# DM1097_Power_Supply.net
KiCad netlist of a schematic drawn in Altium Designer
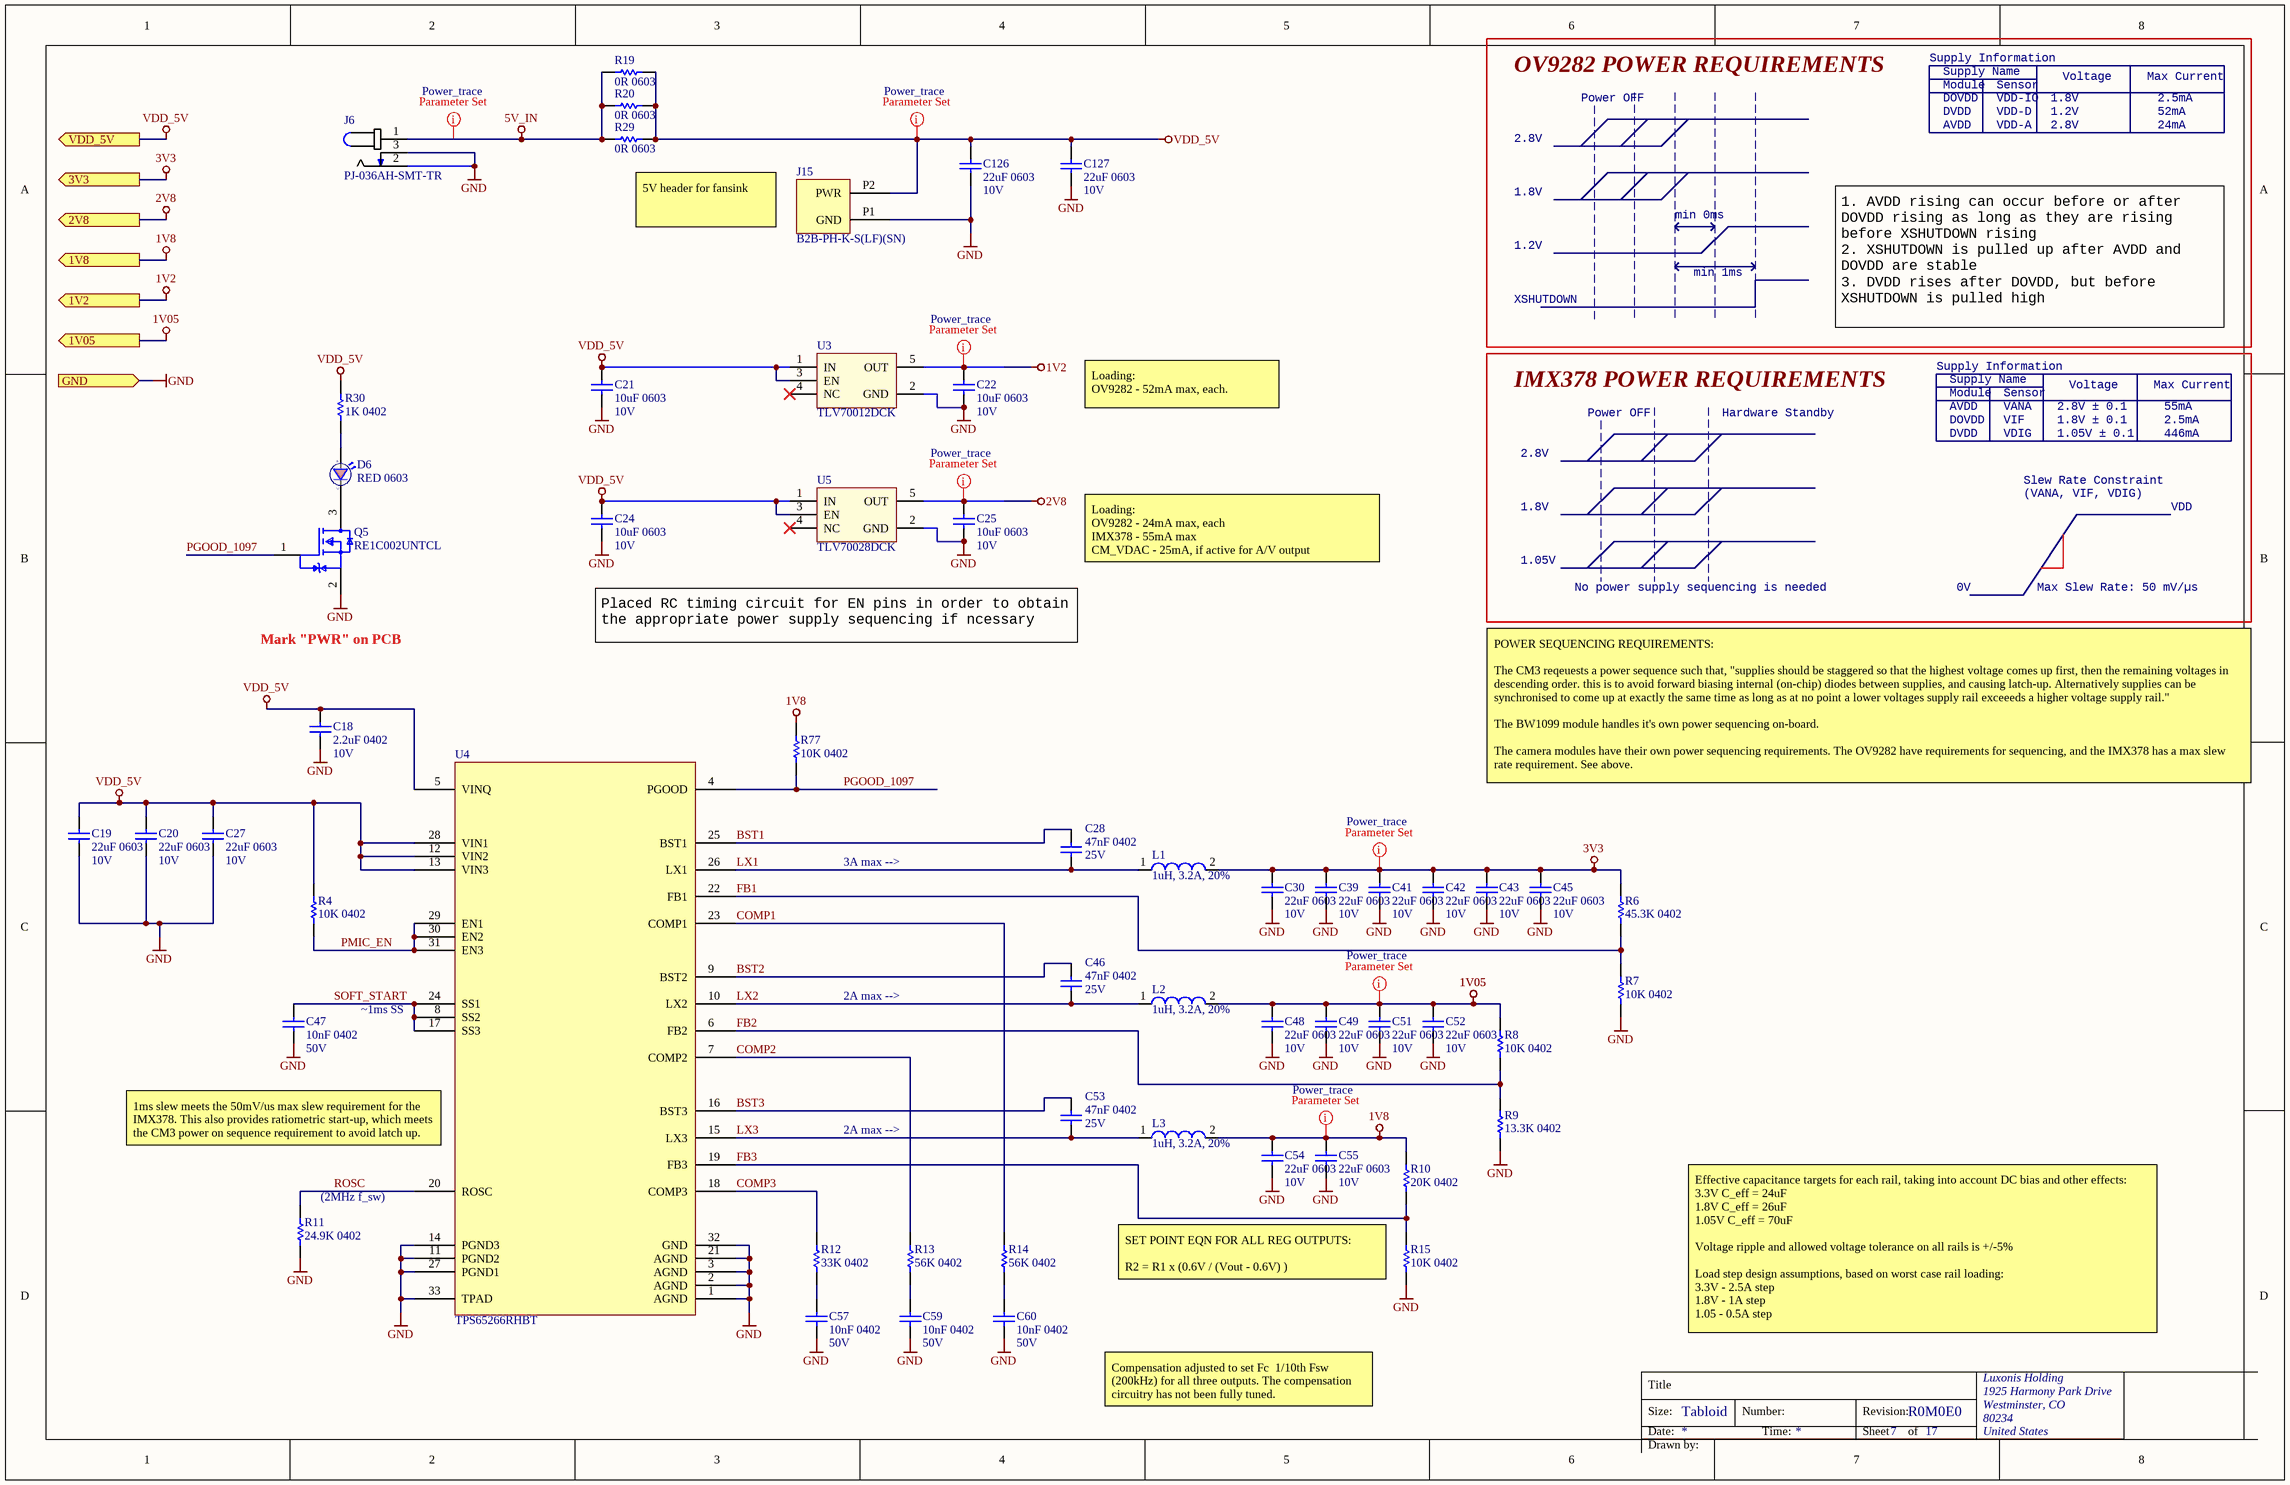
[diagram p0: DM1097_Power_Supply.SchDoc]

(export (version "E")
  (design (tool "Eeschema 10.0.6"))
  (components
    (comp (ref "C18")
      (value "2.2uF 0402")
      (footprint "CAP_Altium_Vault_Generic:CAPC0402(1005)70_N")
      (description "CAP CER 2.2UF 10V X5R 0402 10%")
      (fields (field (name "TOLERANCE") "10%") (field (name "VOLTAGE RATING") "10V"))
      (libsource (lib "LuxonisMaster") (part "GRM155R61A225KE95D"))
    )
    (comp (ref "C19")
      (value "22uF 0603")
      (footprint "CAP_Altium_Vault_Generic:CAPC0603(1608)100_N")
      (description "CAP CER 22UF 10V X5R 0603 20%")
      (fields (field (name "TOLERANCE") "20%") (field (name "VOLTAGE RATING") "10V"))
      (libsource (lib "LuxonisMaster") (part "GRM188R61A226ME15D"))
    )
    (comp (ref "C20")
      (value "22uF 0603")
      (footprint "CAP_Altium_Vault_Generic:CAPC0603(1608)100_N")
      (description "CAP CER 22UF 10V X5R 0603 20%")
      (fields (field (name "TOLERANCE") "20%") (field (name "VOLTAGE RATING") "10V"))
      (libsource (lib "LuxonisMaster") (part "GRM188R61A226ME15D"))
    )
    (comp (ref "C21")
      (value "10uF 0603")
      (footprint "CAP_Altium_Vault_Generic:CAPC0603(1608)100_N")
      (description "CAP CER 10UF 10V X5R 0603 20%")
      (fields (field (name "TOLERANCE") "20%") (field (name "VOLTAGE RATING") "10V"))
      (libsource (lib "LuxonisMaster") (part "GRM188R61A106ME69D"))
    )
    (comp (ref "C22")
      (value "10uF 0603")
      (footprint "CAP_Altium_Vault_Generic:CAPC0603(1608)100_N")
      (description "CAP CER 10UF 10V X5R 0603 20%")
      (fields (field (name "TOLERANCE") "20%") (field (name "VOLTAGE RATING") "10V"))
      (libsource (lib "LuxonisMaster") (part "GRM188R61A106ME69D"))
    )
    (comp (ref "C24")
      (value "10uF 0603")
      (footprint "CAP_Altium_Vault_Generic:CAPC0603(1608)100_N")
      (description "CAP CER 10UF 10V X5R 0603 20%")
      (fields (field (name "TOLERANCE") "20%") (field (name "VOLTAGE RATING") "10V"))
      (libsource (lib "LuxonisMaster") (part "GRM188R61A106ME69D"))
    )
    (comp (ref "C25")
      (value "10uF 0603")
      (footprint "CAP_Altium_Vault_Generic:CAPC0603(1608)100_N")
      (description "CAP CER 10UF 10V X5R 0603 20%")
      (fields (field (name "TOLERANCE") "20%") (field (name "VOLTAGE RATING") "10V"))
      (libsource (lib "LuxonisMaster") (part "GRM188R61A106ME69D"))
    )
    (comp (ref "C27")
      (value "22uF 0603")
      (footprint "CAP_Altium_Vault_Generic:CAPC0603(1608)100_N")
      (description "CAP CER 22UF 10V X5R 0603 20%")
      (fields (field (name "TOLERANCE") "20%") (field (name "VOLTAGE RATING") "10V"))
      (libsource (lib "LuxonisMaster") (part "GRM188R61A226ME15D"))
    )
    (comp (ref "C28")
      (value "47nF 0402")
      (footprint "CAP_Altium_Vault_Generic:CAPC0402(1005)70_N")
      (description "CAP CER 0.047UF 25V X7R 0402 10%")
      (fields
        (field (name "MANUFACTURER") "Murata")
        (field (name "MANUFACTURER PART NUMBER") "GRM155R71E473KA88D")
        (field (name "VOLTAGE") "25V")
      )
      (libsource (lib "LuxonisMaster") (part "GRM155R71E473KA88D"))
    )
    (comp (ref "C30")
      (value "22uF 0603")
      (footprint "CAP_Altium_Vault_Generic:CAPC0603(1608)100_N")
      (description "CAP CER 22UF 10V X5R 0603 20%")
      (fields (field (name "TOLERANCE") "20%") (field (name "VOLTAGE RATING") "10V"))
      (libsource (lib "LuxonisMaster") (part "GRM188R61A226ME15D"))
    )
    (comp (ref "C39")
      (value "22uF 0603")
      (footprint "CAP_Altium_Vault_Generic:CAPC0603(1608)100_N")
      (description "CAP CER 22UF 10V X5R 0603 20%")
      (fields (field (name "TOLERANCE") "20%") (field (name "VOLTAGE RATING") "10V"))
      (libsource (lib "LuxonisMaster") (part "GRM188R61A226ME15D"))
    )
    (comp (ref "C41")
      (value "22uF 0603")
      (footprint "CAP_Altium_Vault_Generic:CAPC0603(1608)100_N")
      (description "CAP CER 22UF 10V X5R 0603 20%")
      (fields (field (name "TOLERANCE") "20%") (field (name "VOLTAGE RATING") "10V"))
      (libsource (lib "LuxonisMaster") (part "GRM188R61A226ME15D"))
    )
    (comp (ref "C42")
      (value "22uF 0603")
      (footprint "CAP_Altium_Vault_Generic:CAPC0603(1608)100_N")
      (description "CAP CER 22UF 10V X5R 0603 20%")
      (fields (field (name "TOLERANCE") "20%") (field (name "VOLTAGE RATING") "10V"))
      (libsource (lib "LuxonisMaster") (part "GRM188R61A226ME15D"))
    )
    (comp (ref "C43")
      (value "22uF 0603")
      (footprint "CAP_Altium_Vault_Generic:CAPC0603(1608)100_N")
      (description "CAP CER 22UF 10V X5R 0603 20%")
      (fields (field (name "TOLERANCE") "20%") (field (name "VOLTAGE RATING") "10V"))
      (libsource (lib "LuxonisMaster") (part "GRM188R61A226ME15D"))
    )
    (comp (ref "C45")
      (value "22uF 0603")
      (footprint "CAP_Altium_Vault_Generic:CAPC0603(1608)100_N")
      (description "CAP CER 22UF 10V X5R 0603 20%")
      (fields (field (name "TOLERANCE") "20%") (field (name "VOLTAGE RATING") "10V"))
      (libsource (lib "LuxonisMaster") (part "GRM188R61A226ME15D"))
    )
    (comp (ref "C46")
      (value "47nF 0402")
      (footprint "CAP_Altium_Vault_Generic:CAPC0402(1005)70_N")
      (description "CAP CER 0.047UF 25V X7R 0402 10%")
      (fields
        (field (name "MANUFACTURER") "Murata")
        (field (name "MANUFACTURER PART NUMBER") "GRM155R71E473KA88D")
        (field (name "VOLTAGE") "25V")
      )
      (libsource (lib "LuxonisMaster") (part "GRM155R71E473KA88D"))
    )
    (comp (ref "C47")
      (value "10nF 0402")
      (footprint "CAP_Altium_Vault_Generic:CAPC0402(1005)60_N")
      (description "CAP CER 10000PF 50V X7R 0402")
      (fields
        (field (name "TOLERANCE") "10%")
        (field (name "VOLTAGE") "25V")
        (field (name "VOLTAGE RATING") "50V")
      )
      (libsource (lib "LuxonisMaster") (part "GRM155R71H103KA88D"))
    )
    (comp (ref "C48")
      (value "22uF 0603")
      (footprint "CAP_Altium_Vault_Generic:CAPC0603(1608)100_N")
      (description "CAP CER 22UF 10V X5R 0603 20%")
      (fields (field (name "TOLERANCE") "20%") (field (name "VOLTAGE RATING") "10V"))
      (libsource (lib "LuxonisMaster") (part "GRM188R61A226ME15D"))
    )
    (comp (ref "C49")
      (value "22uF 0603")
      (footprint "CAP_Altium_Vault_Generic:CAPC0603(1608)100_N")
      (description "CAP CER 22UF 10V X5R 0603 20%")
      (fields (field (name "TOLERANCE") "20%") (field (name "VOLTAGE RATING") "10V"))
      (libsource (lib "LuxonisMaster") (part "GRM188R61A226ME15D"))
    )
    (comp (ref "C51")
      (value "22uF 0603")
      (footprint "CAP_Altium_Vault_Generic:CAPC0603(1608)100_N")
      (description "CAP CER 22UF 10V X5R 0603 20%")
      (fields (field (name "TOLERANCE") "20%") (field (name "VOLTAGE RATING") "10V"))
      (libsource (lib "LuxonisMaster") (part "GRM188R61A226ME15D"))
    )
    (comp (ref "C52")
      (value "22uF 0603")
      (footprint "CAP_Altium_Vault_Generic:CAPC0603(1608)100_N")
      (description "CAP CER 22UF 10V X5R 0603 20%")
      (fields (field (name "TOLERANCE") "20%") (field (name "VOLTAGE RATING") "10V"))
      (libsource (lib "LuxonisMaster") (part "GRM188R61A226ME15D"))
    )
    (comp (ref "C53")
      (value "47nF 0402")
      (footprint "CAP_Altium_Vault_Generic:CAPC0402(1005)70_N")
      (description "CAP CER 0.047UF 25V X7R 0402 10%")
      (fields
        (field (name "MANUFACTURER") "Murata")
        (field (name "MANUFACTURER PART NUMBER") "GRM155R71E473KA88D")
        (field (name "VOLTAGE") "25V")
      )
      (libsource (lib "LuxonisMaster") (part "GRM155R71E473KA88D"))
    )
    (comp (ref "C54")
      (value "22uF 0603")
      (footprint "CAP_Altium_Vault_Generic:CAPC0603(1608)100_N")
      (description "CAP CER 22UF 10V X5R 0603 20%")
      (fields (field (name "TOLERANCE") "20%") (field (name "VOLTAGE RATING") "10V"))
      (libsource (lib "LuxonisMaster") (part "GRM188R61A226ME15D"))
    )
    (comp (ref "C55")
      (value "22uF 0603")
      (footprint "CAP_Altium_Vault_Generic:CAPC0603(1608)100_N")
      (description "CAP CER 22UF 10V X5R 0603 20%")
      (fields (field (name "TOLERANCE") "20%") (field (name "VOLTAGE RATING") "10V"))
      (libsource (lib "LuxonisMaster") (part "GRM188R61A226ME15D"))
    )
    (comp (ref "C57")
      (value "10nF 0402")
      (footprint "CAP_Altium_Vault_Generic:CAPC0402(1005)60_N")
      (description "CAP CER 10000PF 50V X7R 0402")
      (fields
        (field (name "TOLERANCE") "10%")
        (field (name "VOLTAGE") "25V")
        (field (name "VOLTAGE RATING") "50V")
      )
      (libsource (lib "LuxonisMaster") (part "GRM155R71H103KA88D"))
    )
    (comp (ref "C59")
      (value "10nF 0402")
      (footprint "CAP_Altium_Vault_Generic:CAPC0402(1005)60_N")
      (description "CAP CER 10000PF 50V X7R 0402")
      (fields
        (field (name "TOLERANCE") "10%")
        (field (name "VOLTAGE") "25V")
        (field (name "VOLTAGE RATING") "50V")
      )
      (libsource (lib "LuxonisMaster") (part "GRM155R71H103KA88D"))
    )
    (comp (ref "C60")
      (value "10nF 0402")
      (footprint "CAP_Altium_Vault_Generic:CAPC0402(1005)60_N")
      (description "CAP CER 10000PF 50V X7R 0402")
      (fields
        (field (name "TOLERANCE") "10%")
        (field (name "VOLTAGE") "25V")
        (field (name "VOLTAGE RATING") "50V")
      )
      (libsource (lib "LuxonisMaster") (part "GRM155R71H103KA88D"))
    )
    (comp (ref "C126")
      (value "22uF 0603")
      (footprint "CAP_Altium_Vault_Generic:CAPC0603(1608)100_N")
      (description "CAP CER 22UF 10V X5R 0603 20%")
      (fields (field (name "TOLERANCE") "20%") (field (name "VOLTAGE RATING") "10V"))
      (libsource (lib "LuxonisMaster") (part "GRM188R61A226ME15D"))
    )
    (comp (ref "C127")
      (value "22uF 0603")
      (footprint "CAP_Altium_Vault_Generic:CAPC0603(1608)100_N")
      (description "CAP CER 22UF 10V X5R 0603 20%")
      (fields (field (name "TOLERANCE") "20%") (field (name "VOLTAGE RATING") "10V"))
      (libsource (lib "LuxonisMaster") (part "GRM188R61A226ME15D"))
    )
    (comp (ref "D6")
      (value "RED 0603")
      (footprint "LuxonisMaster:SML_D1xx8W")
      (description "LED RED DIFFUSED 0603 SMD Red 620nm LED Indication - Discrete 2.2V 0603 (1608 Metric)")
      (libsource (lib "LuxonisMaster") (part "SML-D12U8WT86"))
    )
    (comp (ref "J6")
      (value "PJ-036AH-SMT-TR")
      (footprint "LuxonisMaster:PJ-036AH-SMT")
      (description "CONN PWR JACK 2X5.5MM SOLDER")
      (libsource (lib "LuxonisMaster") (part "PJ-036AH-SMT-TR"))
    )
    (comp (ref "J15")
      (value "B2B-PH-K-S(LF)(SN)")
      (footprint "LuxonisMaster:B2B-PH-K-S(LF)(SN)")
      (description "CONN HEADER VERT 2POS 2MM")
      (libsource (lib "LuxonisMaster") (part "B2B-PH-K-S(LF)(SN)"))
    )
    (comp (ref "L1")
      (value "1uH, 3.2A, 20%")
      (footprint "LuxonisMaster:DFE252012P-1R0M=P2")
      (description "FIXED IND 1UH 3.2A 42 MOHM SMD")
      (fields
        (field (name "MANUFACTURER") "Murata")
        (field (name "MANUFACTURER PART NUMBER") "DFE252012P-1R0M=P2")
      )
      (libsource (lib "LuxonisMaster") (part "DFE252012P-1R0M=P2"))
    )
    (comp (ref "L2")
      (value "1uH, 3.2A, 20%")
      (footprint "LuxonisMaster:DFE252012P-1R0M=P2")
      (description "FIXED IND 1UH 3.2A 42 MOHM SMD")
      (fields
        (field (name "MANUFACTURER") "Murata")
        (field (name "MANUFACTURER PART NUMBER") "DFE252012P-1R0M=P2")
      )
      (libsource (lib "LuxonisMaster") (part "DFE252012P-1R0M=P2"))
    )
    (comp (ref "L3")
      (value "1uH, 3.2A, 20%")
      (footprint "LuxonisMaster:DFE252012P-1R0M=P2")
      (description "FIXED IND 1UH 3.2A 42 MOHM SMD")
      (fields
        (field (name "MANUFACTURER") "Murata")
        (field (name "MANUFACTURER PART NUMBER") "DFE252012P-1R0M=P2")
      )
      (libsource (lib "LuxonisMaster") (part "DFE252012P-1R0M=P2"))
    )
    (comp (ref "Q5")
      (value "RE1C002UNTCL")
      (footprint "LuxonisMaster:RE1C002UNTCL")
      (description "MOSFET N-CH 20V 0.2A EMT3")
      (libsource (lib "LuxonisMaster") (part "RE1C002UNTCL"))
    )
    (comp (ref "R4")
      (value "10K 0402")
      (footprint "RES_Altium_Vault_Generic:RESC0402(1005)_N")
      (fields (field (name "TOLERANCE") "1%"))
      (libsource (lib "LuxonisMaster") (part "RC0402FR-1310KL"))
    )
    (comp (ref "R6")
      (value "45.3K 0402")
      (footprint "RES_Altium_Vault_Generic:RESC0402(1005)_N")
      (description "RES SMD 45.3K OHM 1% 1/16W 0402")
      (fields (field (name "TOLERANCE") "1%"))
      (libsource (lib "LuxonisMaster") (part "RC0402FR-0745K3L"))
    )
    (comp (ref "R7")
      (value "10K 0402")
      (footprint "RES_Altium_Vault_Generic:RESC0402(1005)_N")
      (fields (field (name "TOLERANCE") "1%"))
      (libsource (lib "LuxonisMaster") (part "RC0402FR-1310KL"))
    )
    (comp (ref "R8")
      (value "10K 0402")
      (footprint "RES_Altium_Vault_Generic:RESC0402(1005)_N")
      (fields (field (name "TOLERANCE") "1%"))
      (libsource (lib "LuxonisMaster") (part "RC0402FR-1310KL"))
    )
    (comp (ref "R9")
      (value "13.3K 0402")
      (footprint "RES_Altium_Vault_Generic:RESC0402(1005)_N")
      (description "RES SMD 13.3K OHM 1% 1/16W 0402")
      (fields (field (name "TOLERANCE") "1%"))
      (libsource (lib "LuxonisMaster") (part "RC0402FR-0713K3L"))
    )
    (comp (ref "R10")
      (value "20K 0402")
      (footprint "RES_Altium_Vault_Generic:RESC0402(1005)_N")
      (fields
        (field (name "MANUFACTURER") "Yageo")
        (field (name "MANUFACTURER PART NUMBER") "RC0402FR-0720KL")
        (field (name "TOLERANCE") "1%")
      )
      (libsource (lib "LuxonisMaster") (part "RC0402FR-0720KL"))
    )
    (comp (ref "R11")
      (value "24.9K 0402")
      (footprint "RES_Altium_Vault_Generic:RESC0402(1005)_N")
      (description "RES SMD 24.9K OHM 1% 1/16W 0402")
      (fields (field (name "TOLERANCE") "1%"))
      (libsource (lib "LuxonisMaster") (part "RC0402FR-0724K9L"))
    )
    (comp (ref "R12")
      (value "33K 0402")
      (footprint "RES_Altium_Vault_Generic:RESC0402(1005)_N")
      (description "RES SMD 33K OHM 1% 1/16W 0402")
      (fields (field (name "TOLERANCE") "1%"))
      (libsource (lib "LuxonisMaster") (part "CRCW040233K0FKED"))
    )
    (comp (ref "R13")
      (value "56K 0402")
      (footprint "RES_Altium_Vault_Generic:RESC0402(1005)_N")
      (fields
        (field (name "MANUFACTURER") "Yageo")
        (field (name "MANUFACTURER PART NUMBER") "RC0402FR-0756KL")
        (field (name "TOLERANCE") "1%")
      )
      (libsource (lib "LuxonisMaster") (part "RC0402FR-0756KL"))
    )
    (comp (ref "R14")
      (value "56K 0402")
      (footprint "RES_Altium_Vault_Generic:RESC0402(1005)_N")
      (fields
        (field (name "MANUFACTURER") "Yageo")
        (field (name "MANUFACTURER PART NUMBER") "RC0402FR-0756KL")
        (field (name "TOLERANCE") "1%")
      )
      (libsource (lib "LuxonisMaster") (part "RC0402FR-0756KL"))
    )
    (comp (ref "R15")
      (value "10K 0402")
      (footprint "RES_Altium_Vault_Generic:RESC0402(1005)_N")
      (fields (field (name "TOLERANCE") "1%"))
      (libsource (lib "LuxonisMaster") (part "RC0402FR-1310KL"))
    )
    (comp (ref "R19")
      (value "0R 0603")
      (footprint "RES_Altium_Vault_Generic:RESC0603(1608)_N")
      (fields (field (name "TOLERANCE") "5%"))
      (libsource (lib "LuxonisMaster") (part "CRCW06030000Z0EA"))
    )
    (comp (ref "R20")
      (value "0R 0603")
      (footprint "RES_Altium_Vault_Generic:RESC0603(1608)_N")
      (fields (field (name "TOLERANCE") "5%"))
      (libsource (lib "LuxonisMaster") (part "CRCW06030000Z0EA"))
    )
    (comp (ref "R29")
      (value "0R 0603")
      (footprint "RES_Altium_Vault_Generic:RESC0603(1608)_N")
      (fields (field (name "TOLERANCE") "5%"))
      (libsource (lib "LuxonisMaster") (part "CRCW06030000Z0EA"))
    )
    (comp (ref "R30")
      (value "1K 0402")
      (footprint "RES_Altium_Vault_Generic:RESC0402(1005)_N")
      (fields (field (name "TOLERANCE") "1%"))
      (libsource (lib "LuxonisMaster") (part "RC0402FR-071KL"))
    )
    (comp (ref "R77")
      (value "10K 0402")
      (footprint "RES_Altium_Vault_Generic:RESC0402(1005)_N")
      (fields (field (name "TOLERANCE") "1%"))
      (libsource (lib "LuxonisMaster") (part "RC0402FR-1310KL"))
    )
    (comp (ref "U3")
      (value "TLV70012DCK")
      (footprint "LuxonisMaster:TLV70012DCK")
      (description "IC REG LINEAR 1.2V 200MA SC70-5")
      (libsource (lib "LuxonisMaster") (part "TLV70012DCK"))
    )
    (comp (ref "U4")
      (value "TPS65266RHBT")
      (footprint "LuxonisMaster:TPS65266RHBT")
      (fields (field (name "MANUFACTURER") "TI"))
      (libsource (lib "LuxonisMaster") (part "TPS65266RHBT"))
    )
    (comp (ref "U5")
      (value "TLV70028DCK")
      (footprint "LuxonisMaster:TLV70028DCK")
      (description "IC REG LINEAR 2.8V 200MA SC70-5 Linear Voltage Regulator IC  1 Output  200mA SC-70-5")
      (libsource (lib "LuxonisMaster") (part "TLV70028DCK"))
    )
  )
  (nets
    (net (code "1") (name "/BST1") (class "Default")
      (node (ref "C28") (pin "1") (pinfunction "1_1") (pintype "passive"))
      (node (ref "U4") (pin "25") (pinfunction "BST1_25") (pintype "passive"))
    )
    (net (code "2") (name "/BST2") (class "Default")
      (node (ref "C46") (pin "1") (pinfunction "1_1") (pintype "passive"))
      (node (ref "U4") (pin "9") (pinfunction "BST2_9") (pintype "passive"))
    )
    (net (code "3") (name "/BST3") (class "Default")
      (node (ref "C53") (pin "1") (pinfunction "1_1") (pintype "passive"))
      (node (ref "U4") (pin "16") (pinfunction "BST3_16") (pintype "passive"))
    )
    (net (code "4") (name "/COMP1") (class "Default")
      (node (ref "R14") (pin "2") (pinfunction "2_2") (pintype "passive"))
      (node (ref "U4") (pin "23") (pinfunction "COMP1_23") (pintype "passive"))
    )
    (net (code "5") (name "/COMP2") (class "Default")
      (node (ref "R13") (pin "2") (pinfunction "2_2") (pintype "passive"))
      (node (ref "U4") (pin "7") (pinfunction "COMP2_7") (pintype "passive"))
    )
    (net (code "6") (name "/COMP3") (class "Default")
      (node (ref "R12") (pin "2") (pinfunction "2_2") (pintype "passive"))
      (node (ref "U4") (pin "18") (pinfunction "COMP3_18") (pintype "passive"))
    )
    (net (code "7") (name "/FB1") (class "Default")
      (node (ref "R6") (pin "1") (pinfunction "1_1") (pintype "passive"))
      (node (ref "R7") (pin "2") (pinfunction "2_2") (pintype "passive"))
      (node (ref "U4") (pin "22") (pinfunction "FB1_22") (pintype "passive"))
    )
    (net (code "8") (name "/FB2") (class "Default")
      (node (ref "R8") (pin "1") (pinfunction "1_1") (pintype "passive"))
      (node (ref "R9") (pin "2") (pinfunction "2_2") (pintype "passive"))
      (node (ref "U4") (pin "6") (pinfunction "FB2_6") (pintype "passive"))
    )
    (net (code "9") (name "/FB3") (class "Default")
      (node (ref "R10") (pin "1") (pinfunction "1_1") (pintype "passive"))
      (node (ref "R15") (pin "2") (pinfunction "2_2") (pintype "passive"))
      (node (ref "U4") (pin "19") (pinfunction "FB3_19") (pintype "passive"))
    )
    (net (code "10") (name "/LX1") (class "Default")
      (node (ref "C28") (pin "2") (pinfunction "2_2") (pintype "passive"))
      (node (ref "L1") (pin "1") (pinfunction "1_1") (pintype "passive"))
      (node (ref "U4") (pin "26") (pinfunction "LX1_26") (pintype "passive"))
    )
    (net (code "11") (name "/LX2") (class "Default")
      (node (ref "C46") (pin "2") (pinfunction "2_2") (pintype "passive"))
      (node (ref "L2") (pin "1") (pinfunction "1_1") (pintype "passive"))
      (node (ref "U4") (pin "10") (pinfunction "LX2_10") (pintype "passive"))
    )
    (net (code "12") (name "/LX3") (class "Default")
      (node (ref "C53") (pin "2") (pinfunction "2_2") (pintype "passive"))
      (node (ref "L3") (pin "1") (pinfunction "1_1") (pintype "passive"))
      (node (ref "U4") (pin "15") (pinfunction "LX3_15") (pintype "passive"))
    )
    (net (code "13") (name "/PGOOD_1097") (class "Default")
      (node (ref "Q5") (pin "1") (pinfunction "Gate_1") (pintype "passive"))
      (node (ref "R77") (pin "1") (pinfunction "1_1") (pintype "passive"))
      (node (ref "U4") (pin "4") (pinfunction "PGOOD_4") (pintype "passive"))
    )
    (net (code "14") (name "/PMIC_EN") (class "Default")
      (node (ref "R4") (pin "1") (pinfunction "1_1") (pintype "passive"))
      (node (ref "U4") (pin "29") (pinfunction "EN1_29") (pintype "passive"))
      (node (ref "U4") (pin "30") (pinfunction "EN2_30") (pintype "passive"))
      (node (ref "U4") (pin "31") (pinfunction "EN3_31") (pintype "passive"))
    )
    (net (code "15") (name "/ROSC") (class "Default")
      (node (ref "R11") (pin "2") (pinfunction "2_2") (pintype "passive"))
      (node (ref "U4") (pin "20") (pinfunction "ROSC_20") (pintype "passive"))
    )
    (net (code "16") (name "/SOFT_START") (class "Default")
      (node (ref "C47") (pin "1") (pinfunction "1_1") (pintype "passive"))
      (node (ref "U4") (pin "17") (pinfunction "SS3_17") (pintype "passive"))
      (node (ref "U4") (pin "24") (pinfunction "SS1_24") (pintype "passive"))
      (node (ref "U4") (pin "8") (pinfunction "SS2_8") (pintype "passive"))
    )
    (net (code "17") (name "1V2") (class "Default")
      (node (ref "C22") (pin "2") (pinfunction "2_2") (pintype "passive"))
      (node (ref "U3") (pin "5") (pinfunction "OUT_5") (pintype "passive"))
    )
    (net (code "18") (name "1V05") (class "Default")
      (node (ref "C48") (pin "1") (pinfunction "1_1") (pintype "passive"))
      (node (ref "C49") (pin "1") (pinfunction "1_1") (pintype "passive"))
      (node (ref "C51") (pin "1") (pinfunction "1_1") (pintype "passive"))
      (node (ref "C52") (pin "1") (pinfunction "1_1") (pintype "passive"))
      (node (ref "L2") (pin "2") (pinfunction "2_2") (pintype "passive"))
      (node (ref "R8") (pin "2") (pinfunction "2_2") (pintype "passive"))
    )
    (net (code "19") (name "1V8") (class "Default")
      (node (ref "C54") (pin "1") (pinfunction "1_1") (pintype "passive"))
      (node (ref "C55") (pin "1") (pinfunction "1_1") (pintype "passive"))
      (node (ref "L3") (pin "2") (pinfunction "2_2") (pintype "passive"))
      (node (ref "R10") (pin "2") (pinfunction "2_2") (pintype "passive"))
      (node (ref "R77") (pin "2") (pinfunction "2_2") (pintype "passive"))
    )
    (net (code "20") (name "2V8") (class "Default")
      (node (ref "C25") (pin "2") (pinfunction "2_2") (pintype "passive"))
      (node (ref "U5") (pin "5") (pinfunction "OUT_5") (pintype "passive"))
    )
    (net (code "21") (name "3V3") (class "Default")
      (node (ref "C30") (pin "1") (pinfunction "1_1") (pintype "passive"))
      (node (ref "C39") (pin "1") (pinfunction "1_1") (pintype "passive"))
      (node (ref "C41") (pin "1") (pinfunction "1_1") (pintype "passive"))
      (node (ref "C42") (pin "1") (pinfunction "1_1") (pintype "passive"))
      (node (ref "C43") (pin "1") (pinfunction "1_1") (pintype "passive"))
      (node (ref "C45") (pin "1") (pinfunction "1_1") (pintype "passive"))
      (node (ref "L1") (pin "2") (pinfunction "2_2") (pintype "passive"))
      (node (ref "R6") (pin "2") (pinfunction "2_2") (pintype "passive"))
    )
    (net (code "22") (name "5V_IN") (class "Default")
      (node (ref "J6") (pin "1") (pinfunction "1_1") (pintype "passive"))
      (node (ref "R19") (pin "2") (pinfunction "2_2") (pintype "passive"))
      (node (ref "R20") (pin "2") (pinfunction "2_2") (pintype "passive"))
      (node (ref "R29") (pin "2") (pinfunction "2_2") (pintype "passive"))
    )
    (net (code "23") (name "GND") (class "Default")
      (node (ref "C126") (pin "2") (pinfunction "2_2") (pintype "passive"))
      (node (ref "C127") (pin "2") (pinfunction "2_2") (pintype "passive"))
      (node (ref "C18") (pin "2") (pinfunction "2_2") (pintype "passive"))
      (node (ref "C19") (pin "2") (pinfunction "2_2") (pintype "passive"))
      (node (ref "C20") (pin "2") (pinfunction "2_2") (pintype "passive"))
      (node (ref "C21") (pin "1") (pinfunction "1_1") (pintype "passive"))
      (node (ref "C22") (pin "1") (pinfunction "1_1") (pintype "passive"))
      (node (ref "C24") (pin "1") (pinfunction "1_1") (pintype "passive"))
      (node (ref "C25") (pin "1") (pinfunction "1_1") (pintype "passive"))
      (node (ref "C27") (pin "2") (pinfunction "2_2") (pintype "passive"))
      (node (ref "C30") (pin "2") (pinfunction "2_2") (pintype "passive"))
      (node (ref "C39") (pin "2") (pinfunction "2_2") (pintype "passive"))
      (node (ref "C41") (pin "2") (pinfunction "2_2") (pintype "passive"))
      (node (ref "C42") (pin "2") (pinfunction "2_2") (pintype "passive"))
      (node (ref "C43") (pin "2") (pinfunction "2_2") (pintype "passive"))
      (node (ref "C45") (pin "2") (pinfunction "2_2") (pintype "passive"))
      (node (ref "C47") (pin "2") (pinfunction "2_2") (pintype "passive"))
      (node (ref "C48") (pin "2") (pinfunction "2_2") (pintype "passive"))
      (node (ref "C49") (pin "2") (pinfunction "2_2") (pintype "passive"))
      (node (ref "C51") (pin "2") (pinfunction "2_2") (pintype "passive"))
      (node (ref "C52") (pin "2") (pinfunction "2_2") (pintype "passive"))
      (node (ref "C54") (pin "2") (pinfunction "2_2") (pintype "passive"))
      (node (ref "C55") (pin "2") (pinfunction "2_2") (pintype "passive"))
      (node (ref "C57") (pin "2") (pinfunction "2_2") (pintype "passive"))
      (node (ref "C59") (pin "2") (pinfunction "2_2") (pintype "passive"))
      (node (ref "C60") (pin "2") (pinfunction "2_2") (pintype "passive"))
      (node (ref "J15") (pin "P1") (pinfunction "GND_P1") (pintype "passive"))
      (node (ref "J6") (pin "2") (pinfunction "2_2") (pintype "passive"))
      (node (ref "J6") (pin "3") (pinfunction "3_3") (pintype "passive"))
      (node (ref "Q5") (pin "2") (pinfunction "Source_2") (pintype "passive"))
      (node (ref "R11") (pin "1") (pinfunction "1_1") (pintype "passive"))
      (node (ref "R15") (pin "1") (pinfunction "1_1") (pintype "passive"))
      (node (ref "R7") (pin "1") (pinfunction "1_1") (pintype "passive"))
      (node (ref "R9") (pin "1") (pinfunction "1_1") (pintype "passive"))
      (node (ref "U3") (pin "2") (pinfunction "GND_2") (pintype "passive"))
      (node (ref "U4") (pin "1") (pinfunction "AGND_1") (pintype "passive"))
      (node (ref "U4") (pin "11") (pinfunction "PGND2_11") (pintype "passive"))
      (node (ref "U4") (pin "14") (pinfunction "PGND3_14") (pintype "passive"))
      (node (ref "U4") (pin "2") (pinfunction "AGND_2") (pintype "passive"))
      (node (ref "U4") (pin "21") (pinfunction "AGND_21") (pintype "passive"))
      (node (ref "U4") (pin "27") (pinfunction "PGND1_27") (pintype "passive"))
      (node (ref "U4") (pin "3") (pinfunction "AGND_3") (pintype "passive"))
      (node (ref "U4") (pin "32") (pinfunction "GND_32") (pintype "passive"))
      (node (ref "U4") (pin "33") (pinfunction "TPAD_33") (pintype "passive"))
      (node (ref "U5") (pin "2") (pinfunction "GND_2") (pintype "passive"))
    )
    (net (code "24") (name "Net-(C57-Pad1)") (class "Default")
      (node (ref "C57") (pin "1") (pinfunction "1_1") (pintype "passive"))
      (node (ref "R12") (pin "1") (pinfunction "1_1") (pintype "passive"))
    )
    (net (code "25") (name "Net-(C59-Pad1)") (class "Default")
      (node (ref "C59") (pin "1") (pinfunction "1_1") (pintype "passive"))
      (node (ref "R13") (pin "1") (pinfunction "1_1") (pintype "passive"))
    )
    (net (code "26") (name "Net-(C60-Pad1)") (class "Default")
      (node (ref "C60") (pin "1") (pinfunction "1_1") (pintype "passive"))
      (node (ref "R14") (pin "1") (pinfunction "1_1") (pintype "passive"))
    )
    (net (code "27") (name "Net-(D6-A)") (class "Default")
      (node (ref "D6") (pin "2") (pinfunction "A_2") (pintype "passive"))
      (node (ref "R30") (pin "1") (pinfunction "1_1") (pintype "passive"))
    )
    (net (code "28") (name "Net-(D6-C)") (class "Default")
      (node (ref "D6") (pin "1") (pinfunction "C_1") (pintype "passive"))
      (node (ref "Q5") (pin "3") (pinfunction "Drain_3") (pintype "passive"))
    )
    (net (code "29") (name "VDD_5V") (class "Default")
      (node (ref "C126") (pin "1") (pinfunction "1_1") (pintype "passive"))
      (node (ref "C127") (pin "1") (pinfunction "1_1") (pintype "passive"))
      (node (ref "C18") (pin "1") (pinfunction "1_1") (pintype "passive"))
      (node (ref "C19") (pin "1") (pinfunction "1_1") (pintype "passive"))
      (node (ref "C20") (pin "1") (pinfunction "1_1") (pintype "passive"))
      (node (ref "C21") (pin "2") (pinfunction "2_2") (pintype "passive"))
      (node (ref "C24") (pin "2") (pinfunction "2_2") (pintype "passive"))
      (node (ref "C27") (pin "1") (pinfunction "1_1") (pintype "passive"))
      (node (ref "J15") (pin "P2") (pinfunction "PWR_P2") (pintype "passive"))
      (node (ref "R19") (pin "1") (pinfunction "1_1") (pintype "passive"))
      (node (ref "R20") (pin "1") (pinfunction "1_1") (pintype "passive"))
      (node (ref "R29") (pin "1") (pinfunction "1_1") (pintype "passive"))
      (node (ref "R30") (pin "2") (pinfunction "2_2") (pintype "passive"))
      (node (ref "R4") (pin "2") (pinfunction "2_2") (pintype "passive"))
      (node (ref "U3") (pin "1") (pinfunction "IN_1") (pintype "passive"))
      (node (ref "U3") (pin "3") (pinfunction "EN_3") (pintype "passive"))
      (node (ref "U4") (pin "12") (pinfunction "VIN2_12") (pintype "passive"))
      (node (ref "U4") (pin "13") (pinfunction "VIN3_13") (pintype "passive"))
      (node (ref "U4") (pin "28") (pinfunction "VIN1_28") (pintype "passive"))
      (node (ref "U4") (pin "5") (pinfunction "VINQ_5") (pintype "passive"))
      (node (ref "U5") (pin "1") (pinfunction "IN_1") (pintype "passive"))
      (node (ref "U5") (pin "3") (pinfunction "EN_3") (pintype "passive"))
    )
    (net (code "30") (name "unconnected-(U3-NC-Pad4)") (class "Default")
      (node (ref "U3") (pin "4") (pinfunction "NC_4") (pintype "passive+no_connect"))
    )
    (net (code "31") (name "unconnected-(U5-NC-Pad4)") (class "Default")
      (node (ref "U5") (pin "4") (pinfunction "NC_4") (pintype "passive+no_connect"))
    )
  )
)
